# Logic.net
KiCad netlist of a schematic drawn in Altium Designer
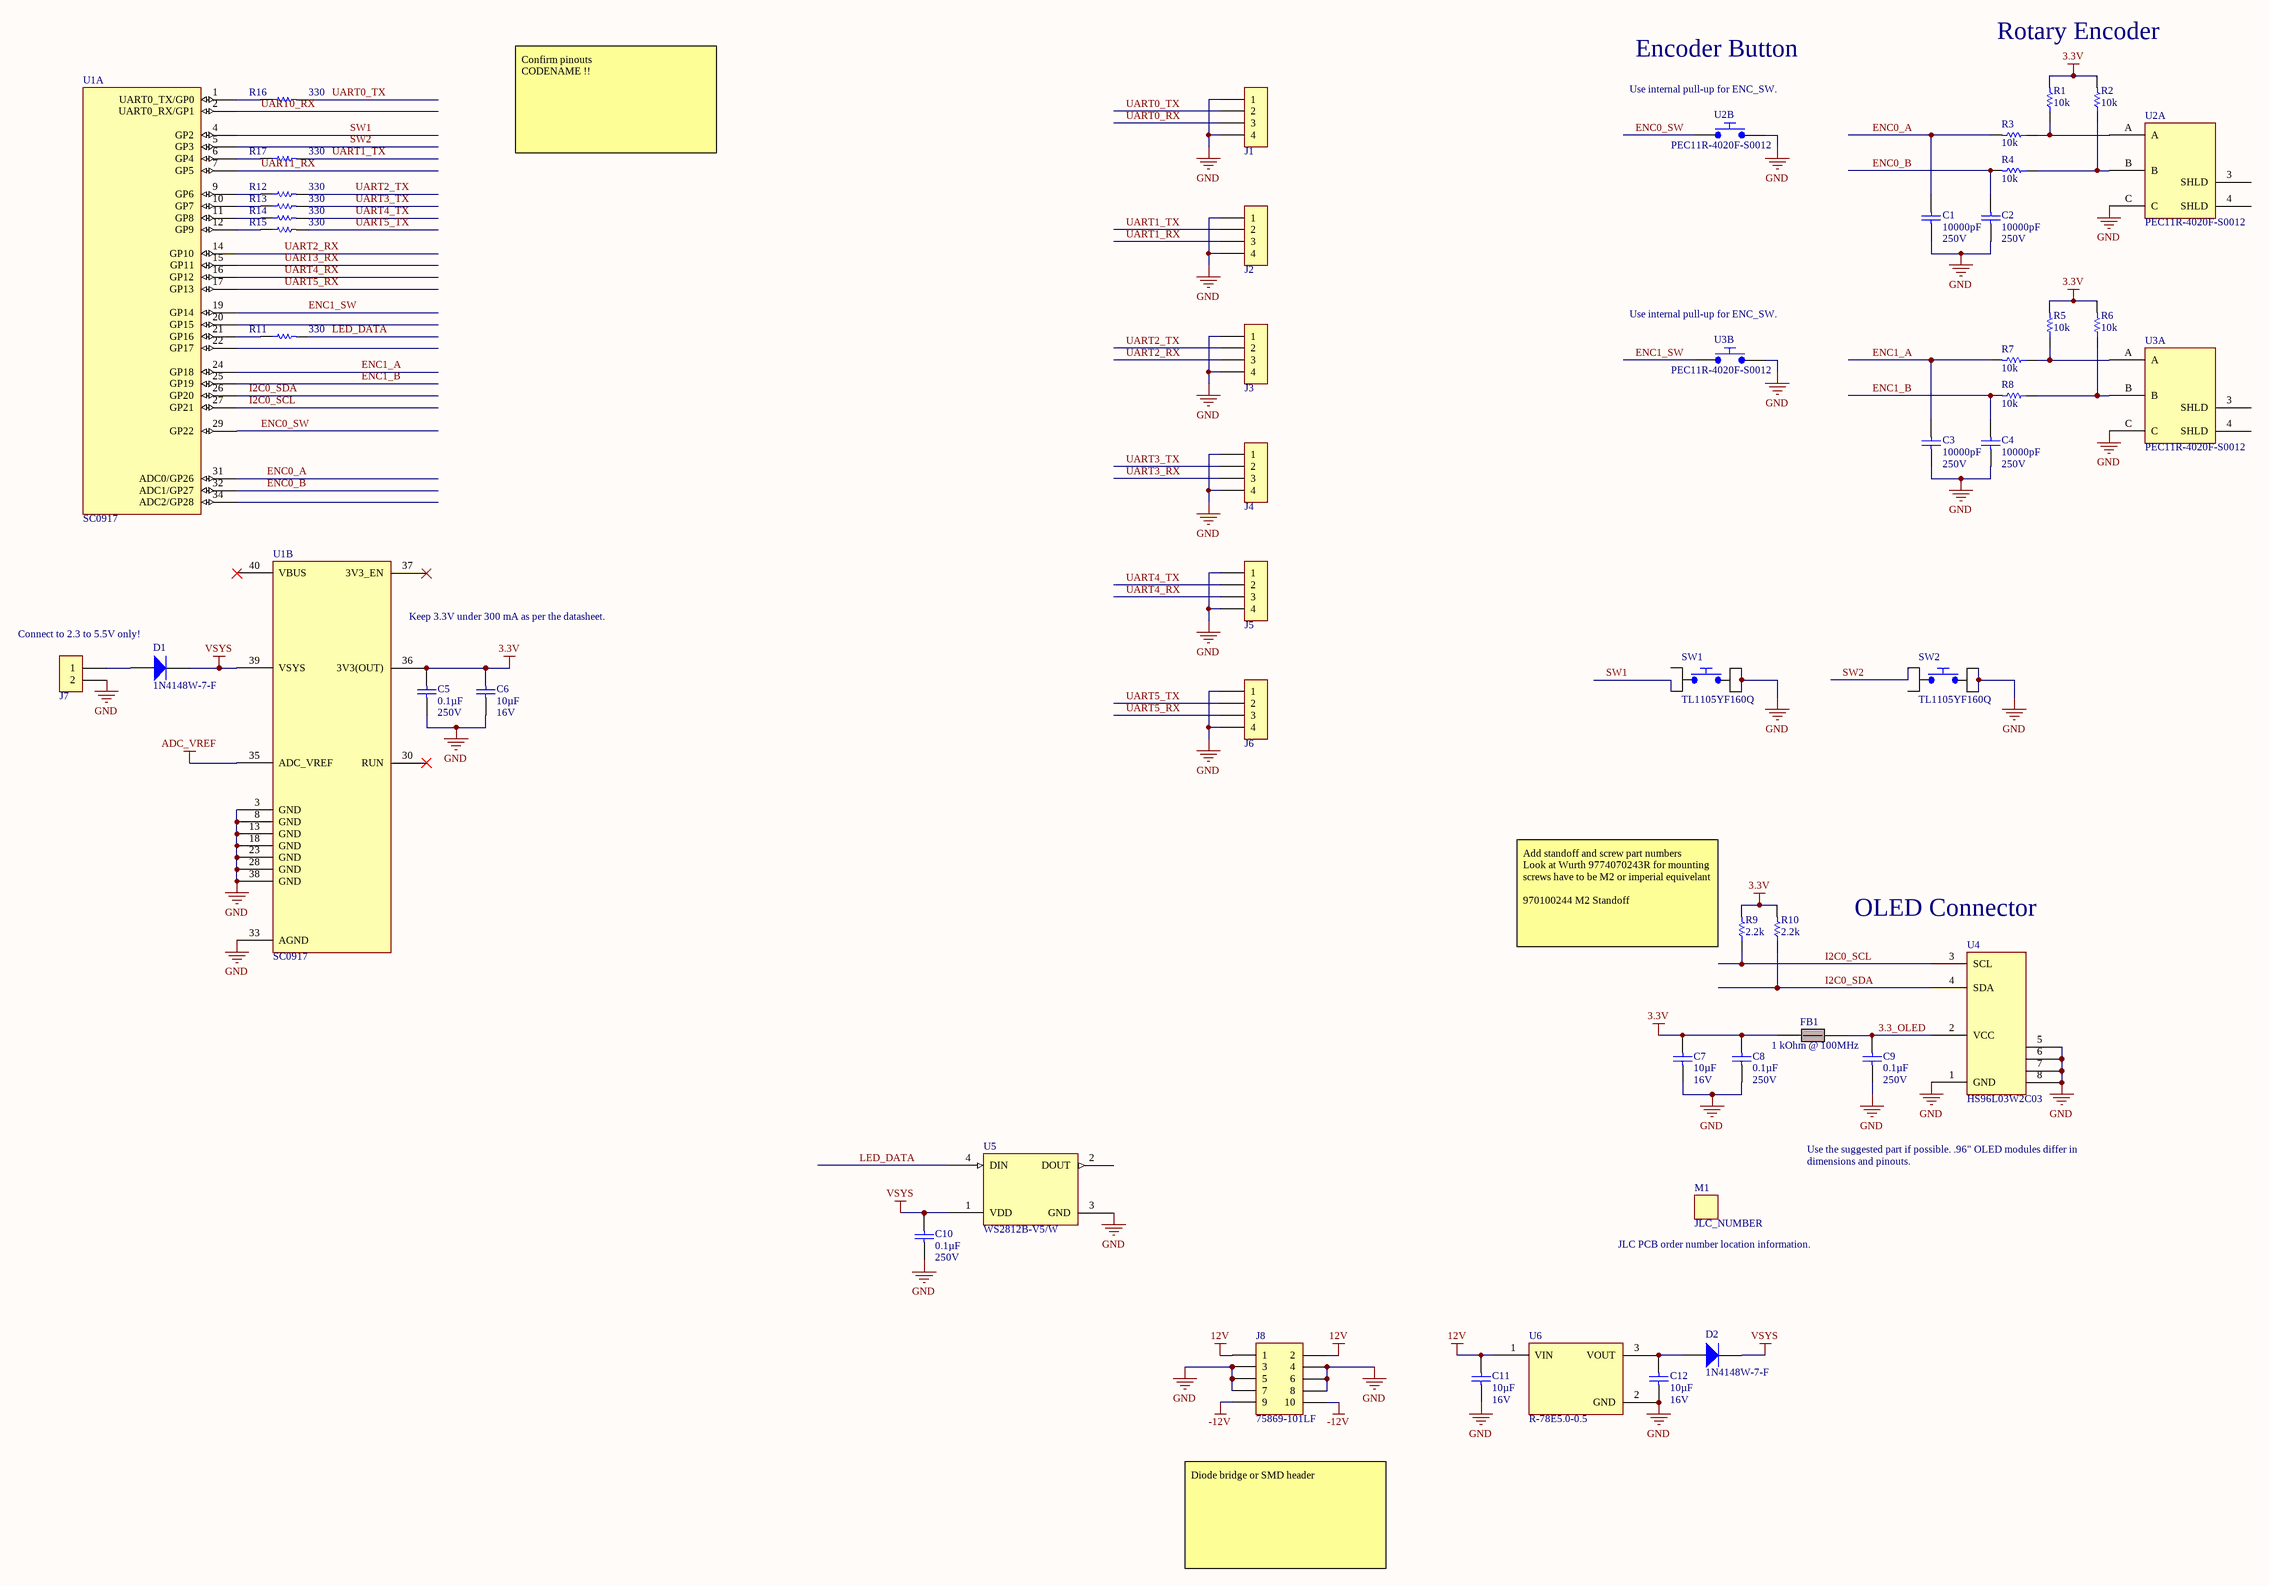
[diagram p0: Logic.SchDoc]

(export (version "E")
  (design (tool "Eeschema 10.0.6"))
  (components
    (comp (ref "C1")
      (value "10000pF")
      (footprint "Chip0805")
      (description "CAP CER 10000PF 250V X7R 0805")
      (fields
        (field (name "VOLTAGE") "250V")
        (field (name "PARTNUMBER") "C2012X7R2E103M125AE")
        (field (name "MANUFACTURER") "TDK Corporation")
      )
      (libsource (lib "Passives") (part "CAP"))
    )
    (comp (ref "C2")
      (value "10000pF")
      (footprint "Chip0805")
      (description "CAP CER 10000PF 250V X7R 0805")
      (fields
        (field (name "VOLTAGE") "250V")
        (field (name "PARTNUMBER") "C2012X7R2E103M125AE")
        (field (name "MANUFACTURER") "TDK Corporation")
      )
      (libsource (lib "Passives") (part "CAP"))
    )
    (comp (ref "C3")
      (value "10000pF")
      (footprint "Chip0805")
      (description "CAP CER 10000PF 250V X7R 0805")
      (fields
        (field (name "VOLTAGE") "250V")
        (field (name "PARTNUMBER") "C2012X7R2E103M125AE")
        (field (name "MANUFACTURER") "TDK Corporation")
      )
      (libsource (lib "Passives") (part "CAP"))
    )
    (comp (ref "C4")
      (value "10000pF")
      (footprint "Chip0805")
      (description "CAP CER 10000PF 250V X7R 0805")
      (fields
        (field (name "VOLTAGE") "250V")
        (field (name "PARTNUMBER") "C2012X7R2E103M125AE")
        (field (name "MANUFACTURER") "TDK Corporation")
      )
      (libsource (lib "Passives") (part "CAP"))
    )
    (comp (ref "C5")
      (value "0.1µF")
      (footprint "Chip0805")
      (description "CAP CER 0.1UF 250V 10% X7T 0805")
      (fields
        (field (name "VOLTAGE") "250V")
        (field (name "PARTNUMBER") "C2012X7T2E104K125AA")
        (field (name "MANUFACTURER") "TDK Corporation")
      )
      (libsource (lib "Passives") (part "CAP"))
    )
    (comp (ref "C6")
      (value "10µF")
      (footprint "Chip0805")
      (description "CAP CER 10UF 16V 10% X5R 0805")
      (fields
        (field (name "VOLTAGE") "16V")
        (field (name "PARTNUMBER") "C2012X5R1C106K125AC")
        (field (name "MANUFACTURER") "TDK Corporation")
      )
      (libsource (lib "Passives") (part "CAP"))
    )
    (comp (ref "C7")
      (value "10µF")
      (footprint "Chip0805")
      (description "CAP CER 10UF 16V 10% X5R 0805")
      (fields
        (field (name "VOLTAGE") "16V")
        (field (name "PARTNUMBER") "C2012X5R1C106K125AC")
        (field (name "MANUFACTURER") "TDK Corporation")
      )
      (libsource (lib "Passives") (part "CAP"))
    )
    (comp (ref "C8")
      (value "0.1µF")
      (footprint "Chip0805")
      (description "CAP CER 0.1UF 250V 10% X7T 0805")
      (fields
        (field (name "VOLTAGE") "250V")
        (field (name "PARTNUMBER") "C2012X7T2E104K125AA")
        (field (name "MANUFACTURER") "TDK Corporation")
      )
      (libsource (lib "Passives") (part "CAP"))
    )
    (comp (ref "C9")
      (value "0.1µF")
      (footprint "Chip0805")
      (description "CAP CER 0.1UF 250V 10% X7T 0805")
      (fields
        (field (name "VOLTAGE") "250V")
        (field (name "PARTNUMBER") "C2012X7T2E104K125AA")
        (field (name "MANUFACTURER") "TDK Corporation")
      )
      (libsource (lib "Passives") (part "CAP"))
    )
    (comp (ref "C10")
      (value "0.1µF")
      (footprint "Chip0805")
      (description "CAP CER 0.1UF 250V 10% X7T 0805")
      (fields
        (field (name "VOLTAGE") "250V")
        (field (name "PARTNUMBER") "C2012X7T2E104K125AA")
        (field (name "MANUFACTURER") "TDK Corporation")
      )
      (libsource (lib "Passives") (part "CAP"))
    )
    (comp (ref "C11")
      (value "10µF")
      (footprint "Chip0805")
      (description "CAP CER 10UF 16V 10% X5R 0805")
      (fields
        (field (name "VOLTAGE") "16V")
        (field (name "PARTNUMBER") "C2012X5R1C106K125AC")
        (field (name "MANUFACTURER") "TDK Corporation")
      )
      (libsource (lib "Passives") (part "CAP"))
    )
    (comp (ref "C12")
      (value "10µF")
      (footprint "Chip0805")
      (description "CAP CER 10UF 16V 10% X5R 0805")
      (fields
        (field (name "VOLTAGE") "16V")
        (field (name "PARTNUMBER") "C2012X5R1C106K125AC")
        (field (name "MANUFACTURER") "TDK Corporation")
      )
      (libsource (lib "Passives") (part "CAP"))
    )
    (comp (ref "D1")
      (value "1N4148W-7-F")
      (footprint "SOD-123")
      (description "DIODE SWITCH 100V 0.15A SOD123")
      (fields (field (name "MANUFACTURER") "Diodes Incorporated"))
      (libsource (lib "Semiconductor") (part "DIODE"))
    )
    (comp (ref "D2")
      (value "1N4148W-7-F")
      (footprint "SOD-123")
      (description "DIODE SWITCH 100V 0.15A SOD123")
      (fields (field (name "MANUFACTURER") "Diodes Incorporated"))
      (libsource (lib "Semiconductor") (part "DIODE"))
    )
    (comp (ref "FB1")
      (value "FERRITE")
      (footprint "Chip0805")
      (description "FERRITE BEAD 1000 OHM .20A 0805")
      (fields
        (field (name "IMPEDANCE @ FREQUENCY") "1 kOhm @ 100MHz")
        (field (name "PARTNUMBER") "74279205")
        (field (name "MANUFACTURER") "Wurth Electronics Inc")
      )
      (libsource (lib "Passives") (part "FERRITE"))
    )
    (comp (ref "J1")
      (value "0533980471")
      (footprint "Molex_0533980471")
      (description "CONN HEADER SMD 4POS 1.25MM")
      (fields (field (name "MANUFACTURER") "Molex"))
      (libsource (lib "Connectors") (part "HEADER_1x4"))
    )
    (comp (ref "J2")
      (value "0533980471")
      (footprint "Molex_0533980471")
      (description "CONN HEADER SMD 4POS 1.25MM")
      (fields (field (name "MANUFACTURER") "Molex"))
      (libsource (lib "Connectors") (part "HEADER_1x4"))
    )
    (comp (ref "J3")
      (value "0533980471")
      (footprint "Molex_0533980471")
      (description "CONN HEADER SMD 4POS 1.25MM")
      (fields (field (name "MANUFACTURER") "Molex"))
      (libsource (lib "Connectors") (part "HEADER_1x4"))
    )
    (comp (ref "J4")
      (value "0533980471")
      (footprint "Molex_0533980471")
      (description "CONN HEADER SMD 4POS 1.25MM")
      (fields (field (name "MANUFACTURER") "Molex"))
      (libsource (lib "Connectors") (part "HEADER_1x4"))
    )
    (comp (ref "J5")
      (value "0533980471")
      (footprint "Molex_0533980471")
      (description "CONN HEADER SMD 4POS 1.25MM")
      (fields (field (name "MANUFACTURER") "Molex"))
      (libsource (lib "Connectors") (part "HEADER_1x4"))
    )
    (comp (ref "J6")
      (value "0533980471")
      (footprint "Molex_0533980471")
      (description "CONN HEADER SMD 4POS 1.25MM")
      (fields (field (name "MANUFACTURER") "Molex"))
      (libsource (lib "Connectors") (part "HEADER_1x4"))
    )
    (comp (ref "J7")
      (value "3-644456-2")
      (footprint "TE_3-644456-2")
      (description "CONN HEADER VERT 2POS .100 TIN")
      (fields (field (name "MANUFACTURER") "TE Connectivity"))
      (libsource (lib "Connectors") (part "HEADER_1x2"))
    )
    (comp (ref "J8")
      (value "75869-101LF")
      (footprint "IDC_100_2x5")
      (description "CONN HEADER 10POS DUAL VERT PCB")
      (fields (field (name "MANUFACTURER") "FCI"))
      (libsource (lib "Connectors") (part "HEADER_2x5_ALT"))
    )
    (comp (ref "M1")
      (value "JLC_NUMBER")
      (footprint "JLC_NUMBER")
      (description "JLC Order Number Location")
      (libsource (lib "Mechanical") (part "MECH_NO_BOM"))
    )
    (comp (ref "R1")
      (value "10k")
      (footprint "Chip0805")
      (description "RES 10.0K OHM 1/8W 1% 0805 SMD")
      (fields (field (name "PARTNUMBER") "CRCW080510K0FKEA") (field (name "MANUFACTURER") "Vishay Dale"))
      (libsource (lib "Passives") (part "RES"))
    )
    (comp (ref "R2")
      (value "10k")
      (footprint "Chip0805")
      (description "RES 10.0K OHM 1/8W 1% 0805 SMD")
      (fields (field (name "PARTNUMBER") "CRCW080510K0FKEA") (field (name "MANUFACTURER") "Vishay Dale"))
      (libsource (lib "Passives") (part "RES"))
    )
    (comp (ref "R3")
      (value "10k")
      (footprint "Chip0805")
      (description "RES 10.0K OHM 1/8W 1% 0805 SMD")
      (fields (field (name "PARTNUMBER") "CRCW080510K0FKEA") (field (name "MANUFACTURER") "Vishay Dale"))
      (libsource (lib "Passives") (part "RES"))
    )
    (comp (ref "R4")
      (value "10k")
      (footprint "Chip0805")
      (description "RES 10.0K OHM 1/8W 1% 0805 SMD")
      (fields (field (name "PARTNUMBER") "CRCW080510K0FKEA") (field (name "MANUFACTURER") "Vishay Dale"))
      (libsource (lib "Passives") (part "RES"))
    )
    (comp (ref "R5")
      (value "10k")
      (footprint "Chip0805")
      (description "RES 10.0K OHM 1/8W 1% 0805 SMD")
      (fields (field (name "PARTNUMBER") "CRCW080510K0FKEA") (field (name "MANUFACTURER") "Vishay Dale"))
      (libsource (lib "Passives") (part "RES"))
    )
    (comp (ref "R6")
      (value "10k")
      (footprint "Chip0805")
      (description "RES 10.0K OHM 1/8W 1% 0805 SMD")
      (fields (field (name "PARTNUMBER") "CRCW080510K0FKEA") (field (name "MANUFACTURER") "Vishay Dale"))
      (libsource (lib "Passives") (part "RES"))
    )
    (comp (ref "R7")
      (value "10k")
      (footprint "Chip0805")
      (description "RES 10.0K OHM 1/8W 1% 0805 SMD")
      (fields (field (name "PARTNUMBER") "CRCW080510K0FKEA") (field (name "MANUFACTURER") "Vishay Dale"))
      (libsource (lib "Passives") (part "RES"))
    )
    (comp (ref "R8")
      (value "10k")
      (footprint "Chip0805")
      (description "RES 10.0K OHM 1/8W 1% 0805 SMD")
      (fields (field (name "PARTNUMBER") "CRCW080510K0FKEA") (field (name "MANUFACTURER") "Vishay Dale"))
      (libsource (lib "Passives") (part "RES"))
    )
    (comp (ref "R9")
      (value "2.2k")
      (footprint "Chip0805")
      (description "RES 2.20K OHM 1/8W 1% 0805 SMD")
      (fields (field (name "PARTNUMBER") "CRCW08052K20FKEA") (field (name "MANUFACTURER") "Vishay Dale"))
      (libsource (lib "Passives") (part "RES"))
    )
    (comp (ref "R10")
      (value "2.2k")
      (footprint "Chip0805")
      (description "RES 2.20K OHM 1/8W 1% 0805 SMD")
      (fields (field (name "PARTNUMBER") "CRCW08052K20FKEA") (field (name "MANUFACTURER") "Vishay Dale"))
      (libsource (lib "Passives") (part "RES"))
    )
    (comp (ref "R11")
      (value "330")
      (footprint "Chip0805")
      (description "RES 330 OHM 1/8W 1% 0805 SMD")
      (fields (field (name "PARTNUMBER") "CRCW0805330RFKEA") (field (name "MANUFACTURER") "Vishay Dale"))
      (libsource (lib "Passives") (part "RES"))
    )
    (comp (ref "R12")
      (value "330")
      (footprint "Chip0805")
      (description "RES 330 OHM 1/8W 1% 0805 SMD")
      (fields (field (name "PARTNUMBER") "CRCW0805330RFKEA") (field (name "MANUFACTURER") "Vishay Dale"))
      (libsource (lib "Passives") (part "RES"))
    )
    (comp (ref "R13")
      (value "330")
      (footprint "Chip0805")
      (description "RES 330 OHM 1/8W 1% 0805 SMD")
      (fields (field (name "PARTNUMBER") "CRCW0805330RFKEA") (field (name "MANUFACTURER") "Vishay Dale"))
      (libsource (lib "Passives") (part "RES"))
    )
    (comp (ref "R14")
      (value "330")
      (footprint "Chip0805")
      (description "RES 330 OHM 1/8W 1% 0805 SMD")
      (fields (field (name "PARTNUMBER") "CRCW0805330RFKEA") (field (name "MANUFACTURER") "Vishay Dale"))
      (libsource (lib "Passives") (part "RES"))
    )
    (comp (ref "R15")
      (value "330")
      (footprint "Chip0805")
      (description "RES 330 OHM 1/8W 1% 0805 SMD")
      (fields (field (name "PARTNUMBER") "CRCW0805330RFKEA") (field (name "MANUFACTURER") "Vishay Dale"))
      (libsource (lib "Passives") (part "RES"))
    )
    (comp (ref "R16")
      (value "330")
      (footprint "Chip0805")
      (description "RES 330 OHM 1/8W 1% 0805 SMD")
      (fields (field (name "PARTNUMBER") "CRCW0805330RFKEA") (field (name "MANUFACTURER") "Vishay Dale"))
      (libsource (lib "Passives") (part "RES"))
    )
    (comp (ref "R17")
      (value "330")
      (footprint "Chip0805")
      (description "RES 330 OHM 1/8W 1% 0805 SMD")
      (fields (field (name "PARTNUMBER") "CRCW0805330RFKEA") (field (name "MANUFACTURER") "Vishay Dale"))
      (libsource (lib "Passives") (part "RES"))
    )
    (comp (ref "SW1")
      (value "TL1105YF160Q")
      (footprint "E-Switch_TL1105YF")
      (description "SWITCH TACTILE SPST-NO 0.05A 12V")
      (fields (field (name "MANUFACTURER") "E-Switch"))
      (libsource (lib "Switches") (part "SWITCH_SPST_4PIN"))
    )
    (comp (ref "SW2")
      (value "TL1105YF160Q")
      (footprint "E-Switch_TL1105YF")
      (description "SWITCH TACTILE SPST-NO 0.05A 12V")
      (fields (field (name "MANUFACTURER") "E-Switch"))
      (libsource (lib "Switches") (part "SWITCH_SPST_4PIN"))
    )
    (comp (ref "U1")
      (value "SC0917")
      (footprint "RASPBERRY_PI_PICO_H")
      (description "RASPBERRY PI PICO H")
      (fields (field (name "MANUFACTURER") "Raspberry Pi"))
      (libsource (lib "ICs") (part "PI_PICO_H_SC0917"))
    )
    (comp (ref "U2")
      (value "PEC11R-4020F-S0012")
      (footprint "BOURNS_PEC11R-4020F-S")
      (description "ROTARY ENCODER MECHANICAL 12PPR")
      (fields (field (name "MANUFACTURER") "Bourns Inc."))
      (libsource (lib "Miscellaneous") (part "ROTARY_ENCODER_SWITCH"))
    )
    (comp (ref "U3")
      (value "PEC11R-4020F-S0012")
      (footprint "BOURNS_PEC11R-4020F-S")
      (description "ROTARY ENCODER MECHANICAL 12PPR")
      (fields (field (name "MANUFACTURER") "Bourns Inc."))
      (libsource (lib "") (part "ROTARY_ENCODER_SWITCH_1"))
    )
    (comp (ref "U4")
      (value "HS96L03W2C03")
      (footprint "HS_HS96L03W2C03")
      (description "0.96\" I2C OLED MODULE")
      (fields (field (name "MANUFACTURER") "HS"))
      (libsource (lib "ICs") (part "HS_HS96L03W2C03"))
    )
    (comp (ref "U5")
      (value "WS2812B-V5/W")
      (footprint "WS2812B")
      (description "Addressable RGB LED")
      (fields (field (name "MANUFACTURER") "Worldsemi"))
      (libsource (lib "Optoelectronics") (part "WORLDSEMI_WS2812B"))
    )
    (comp (ref "U6")
      (value "R-78E5.0-0.5")
      (footprint "3-SIP_Module")
      (description "DC DC CONVERTER 5V 3W")
      (fields (field (name "MANUFACTURER") "Recom Power"))
      (libsource (lib "ICs") (part "3-SIP_Module"))
    )
  )
  (nets
    (net (code "1") (name "-12V") (class "Default")
      (node (ref "J8") (pin "10") (pinfunction "10_10") (pintype "passive"))
      (node (ref "J8") (pin "9") (pinfunction "9_9") (pintype "passive"))
    )
    (net (code "2") (name "/3.3_OLED") (class "Default")
      (node (ref "C9") (pin "2") (pinfunction "2_2") (pintype "passive"))
      (node (ref "FB1") (pin "2") (pinfunction "2_2") (pintype "passive"))
      (node (ref "U4") (pin "2") (pinfunction "VCC_2") (pintype "passive"))
    )
    (net (code "3") (name "/ENC0_A") (class "Default")
      (node (ref "C1") (pin "2") (pinfunction "2_2") (pintype "passive"))
      (node (ref "R3") (pin "2") (pinfunction "2_2") (pintype "passive"))
      (node (ref "U1") (pin "31") (pinfunction "ADC0/GP26_31") (pintype "bidirectional"))
    )
    (net (code "4") (name "/ENC0_B") (class "Default")
      (node (ref "C2") (pin "2") (pinfunction "2_2") (pintype "passive"))
      (node (ref "R4") (pin "2") (pinfunction "2_2") (pintype "passive"))
      (node (ref "U1") (pin "32") (pinfunction "ADC1/GP27_32") (pintype "bidirectional"))
    )
    (net (code "5") (name "/ENC0_SW") (class "Default")
      (node (ref "U1") (pin "29") (pinfunction "GP22_29") (pintype "bidirectional"))
      (node (ref "U2") (pin "2") (pinfunction "2_2") (pintype "passive"))
    )
    (net (code "6") (name "/ENC1_A") (class "Default")
      (node (ref "C3") (pin "2") (pinfunction "2_2") (pintype "passive"))
      (node (ref "R7") (pin "2") (pinfunction "2_2") (pintype "passive"))
      (node (ref "U1") (pin "24") (pinfunction "GP18_24") (pintype "bidirectional"))
    )
    (net (code "7") (name "/ENC1_B") (class "Default")
      (node (ref "C4") (pin "2") (pinfunction "2_2") (pintype "passive"))
      (node (ref "R8") (pin "2") (pinfunction "2_2") (pintype "passive"))
      (node (ref "U1") (pin "25") (pinfunction "GP19_25") (pintype "bidirectional"))
    )
    (net (code "8") (name "/ENC1_SW") (class "Default")
      (node (ref "U1") (pin "19") (pinfunction "GP14_19") (pintype "bidirectional"))
      (node (ref "U3") (pin "2") (pinfunction "2_2") (pintype "passive"))
    )
    (net (code "9") (name "/I2C0_SCL") (class "Default")
      (node (ref "R9") (pin "1") (pinfunction "1_1") (pintype "passive"))
      (node (ref "U1") (pin "27") (pinfunction "GP21_27") (pintype "bidirectional"))
      (node (ref "U4") (pin "3") (pinfunction "SCL_3") (pintype "passive"))
    )
    (net (code "10") (name "/I2C0_SDA") (class "Default")
      (node (ref "R10") (pin "1") (pinfunction "1_1") (pintype "passive"))
      (node (ref "U1") (pin "26") (pinfunction "GP20_26") (pintype "bidirectional"))
      (node (ref "U4") (pin "4") (pinfunction "SDA_4") (pintype "passive"))
    )
    (net (code "11") (name "/LED_DATA") (class "Default")
      (node (ref "R11") (pin "2") (pinfunction "2_2") (pintype "passive"))
      (node (ref "U5") (pin "4") (pinfunction "DIN_4") (pintype "input"))
    )
    (net (code "12") (name "/SW1") (class "Default")
      (node (ref "SW1") (pin "2") (pinfunction "2_2") (pintype "passive"))
      (node (ref "U1") (pin "4") (pinfunction "GP2_4") (pintype "bidirectional"))
    )
    (net (code "13") (name "/SW2") (class "Default")
      (node (ref "SW2") (pin "1") (pinfunction "1_1") (pintype "passive"))
      (node (ref "U1") (pin "5") (pinfunction "GP3_5") (pintype "bidirectional"))
    )
    (net (code "14") (name "/UART0_RX") (class "Default")
      (node (ref "J1") (pin "3") (pinfunction "3_3") (pintype "passive"))
      (node (ref "U1") (pin "2") (pinfunction "UART0_RX/GP1_2") (pintype "bidirectional"))
    )
    (net (code "15") (name "/UART0_TX") (class "Default")
      (node (ref "J1") (pin "2") (pinfunction "2_2") (pintype "passive"))
      (node (ref "R16") (pin "2") (pinfunction "2_2") (pintype "passive"))
    )
    (net (code "16") (name "/UART1_RX") (class "Default")
      (node (ref "J2") (pin "3") (pinfunction "3_3") (pintype "passive"))
      (node (ref "U1") (pin "7") (pinfunction "GP5_7") (pintype "bidirectional"))
    )
    (net (code "17") (name "/UART1_TX") (class "Default")
      (node (ref "J2") (pin "2") (pinfunction "2_2") (pintype "passive"))
      (node (ref "R17") (pin "2") (pinfunction "2_2") (pintype "passive"))
    )
    (net (code "18") (name "/UART2_RX") (class "Default")
      (node (ref "J3") (pin "3") (pinfunction "3_3") (pintype "passive"))
      (node (ref "U1") (pin "14") (pinfunction "GP10_14") (pintype "bidirectional"))
    )
    (net (code "19") (name "/UART2_TX") (class "Default")
      (node (ref "J3") (pin "2") (pinfunction "2_2") (pintype "passive"))
      (node (ref "R12") (pin "2") (pinfunction "2_2") (pintype "passive"))
    )
    (net (code "20") (name "/UART3_RX") (class "Default")
      (node (ref "J4") (pin "3") (pinfunction "3_3") (pintype "passive"))
      (node (ref "U1") (pin "15") (pinfunction "GP11_15") (pintype "bidirectional"))
    )
    (net (code "21") (name "/UART3_TX") (class "Default")
      (node (ref "J4") (pin "2") (pinfunction "2_2") (pintype "passive"))
      (node (ref "R13") (pin "2") (pinfunction "2_2") (pintype "passive"))
    )
    (net (code "22") (name "/UART4_RX") (class "Default")
      (node (ref "J5") (pin "3") (pinfunction "3_3") (pintype "passive"))
      (node (ref "U1") (pin "16") (pinfunction "GP12_16") (pintype "bidirectional"))
    )
    (net (code "23") (name "/UART4_TX") (class "Default")
      (node (ref "J5") (pin "2") (pinfunction "2_2") (pintype "passive"))
      (node (ref "R14") (pin "2") (pinfunction "2_2") (pintype "passive"))
    )
    (net (code "24") (name "/UART5_RX") (class "Default")
      (node (ref "J6") (pin "3") (pinfunction "3_3") (pintype "passive"))
      (node (ref "U1") (pin "17") (pinfunction "GP13_17") (pintype "bidirectional"))
    )
    (net (code "25") (name "/UART5_TX") (class "Default")
      (node (ref "J6") (pin "2") (pinfunction "2_2") (pintype "passive"))
      (node (ref "R15") (pin "2") (pinfunction "2_2") (pintype "passive"))
    )
    (net (code "26") (name "3.3V") (class "Default")
      (node (ref "C5") (pin "2") (pinfunction "2_2") (pintype "passive"))
      (node (ref "C6") (pin "2") (pinfunction "2_2") (pintype "passive"))
      (node (ref "C7") (pin "2") (pinfunction "2_2") (pintype "passive"))
      (node (ref "C8") (pin "2") (pinfunction "2_2") (pintype "passive"))
      (node (ref "FB1") (pin "1") (pinfunction "1_1") (pintype "passive"))
      (node (ref "R1") (pin "2") (pinfunction "2_2") (pintype "passive"))
      (node (ref "R10") (pin "2") (pinfunction "2_2") (pintype "passive"))
      (node (ref "R2") (pin "2") (pinfunction "2_2") (pintype "passive"))
      (node (ref "R5") (pin "2") (pinfunction "2_2") (pintype "passive"))
      (node (ref "R6") (pin "2") (pinfunction "2_2") (pintype "passive"))
      (node (ref "R9") (pin "2") (pinfunction "2_2") (pintype "passive"))
      (node (ref "U1") (pin "36") (pinfunction "3V3(OUT)_36") (pintype "passive"))
    )
    (net (code "27") (name "12V") (class "Default")
      (node (ref "C11") (pin "2") (pinfunction "2_2") (pintype "passive"))
      (node (ref "J8") (pin "1") (pinfunction "1_1") (pintype "passive"))
      (node (ref "J8") (pin "2") (pinfunction "2_2") (pintype "passive"))
      (node (ref "U6") (pin "1") (pinfunction "VIN_1") (pintype "passive"))
    )
    (net (code "28") (name "ADC_VREF") (class "Default")
      (node (ref "U1") (pin "35") (pinfunction "ADC_VREF_35") (pintype "passive"))
    )
    (net (code "29") (name "GND") (class "Default")
      (node (ref "C1") (pin "1") (pinfunction "1_1") (pintype "passive"))
      (node (ref "C10") (pin "1") (pinfunction "1_1") (pintype "passive"))
      (node (ref "C11") (pin "1") (pinfunction "1_1") (pintype "passive"))
      (node (ref "C12") (pin "1") (pinfunction "1_1") (pintype "passive"))
      (node (ref "C2") (pin "1") (pinfunction "1_1") (pintype "passive"))
      (node (ref "C3") (pin "1") (pinfunction "1_1") (pintype "passive"))
      (node (ref "C4") (pin "1") (pinfunction "1_1") (pintype "passive"))
      (node (ref "C5") (pin "1") (pinfunction "1_1") (pintype "passive"))
      (node (ref "C6") (pin "1") (pinfunction "1_1") (pintype "passive"))
      (node (ref "C7") (pin "1") (pinfunction "1_1") (pintype "passive"))
      (node (ref "C8") (pin "1") (pinfunction "1_1") (pintype "passive"))
      (node (ref "C9") (pin "1") (pinfunction "1_1") (pintype "passive"))
      (node (ref "J1") (pin "1") (pinfunction "1_1") (pintype "passive"))
      (node (ref "J1") (pin "4") (pinfunction "4_4") (pintype "passive"))
      (node (ref "J2") (pin "1") (pinfunction "1_1") (pintype "passive"))
      (node (ref "J2") (pin "4") (pinfunction "4_4") (pintype "passive"))
      (node (ref "J3") (pin "1") (pinfunction "1_1") (pintype "passive"))
      (node (ref "J3") (pin "4") (pinfunction "4_4") (pintype "passive"))
      (node (ref "J4") (pin "1") (pinfunction "1_1") (pintype "passive"))
      (node (ref "J4") (pin "4") (pinfunction "4_4") (pintype "passive"))
      (node (ref "J5") (pin "1") (pinfunction "1_1") (pintype "passive"))
      (node (ref "J5") (pin "4") (pinfunction "4_4") (pintype "passive"))
      (node (ref "J6") (pin "1") (pinfunction "1_1") (pintype "passive"))
      (node (ref "J6") (pin "4") (pinfunction "4_4") (pintype "passive"))
      (node (ref "J7") (pin "2") (pinfunction "2_2") (pintype "passive"))
      (node (ref "J8") (pin "3") (pinfunction "3_3") (pintype "passive"))
      (node (ref "J8") (pin "4") (pinfunction "4_4") (pintype "passive"))
      (node (ref "J8") (pin "5") (pinfunction "5_5") (pintype "passive"))
      (node (ref "J8") (pin "6") (pinfunction "6_6") (pintype "passive"))
      (node (ref "J8") (pin "7") (pinfunction "7_7") (pintype "passive"))
      (node (ref "J8") (pin "8") (pinfunction "8_8") (pintype "passive"))
      (node (ref "SW1") (pin "3") (pinfunction "3_3") (pintype "passive"))
      (node (ref "SW1") (pin "4") (pinfunction "4_4") (pintype "passive"))
      (node (ref "SW2") (pin "3") (pinfunction "3_3") (pintype "passive"))
      (node (ref "SW2") (pin "4") (pinfunction "4_4") (pintype "passive"))
      (node (ref "U1") (pin "13") (pinfunction "GND_13") (pintype "passive"))
      (node (ref "U1") (pin "18") (pinfunction "GND_18") (pintype "passive"))
      (node (ref "U1") (pin "23") (pinfunction "GND_23") (pintype "passive"))
      (node (ref "U1") (pin "28") (pinfunction "GND_28") (pintype "passive"))
      (node (ref "U1") (pin "3") (pinfunction "GND_3") (pintype "passive"))
      (node (ref "U1") (pin "33") (pinfunction "AGND_33") (pintype "passive"))
      (node (ref "U1") (pin "38") (pinfunction "GND_38") (pintype "passive"))
      (node (ref "U1") (pin "8") (pinfunction "GND_8") (pintype "passive"))
      (node (ref "U2") (pin "1") (pinfunction "1_1") (pintype "passive"))
      (node (ref "U2") (pin "C") (pinfunction "C_C") (pintype "passive"))
      (node (ref "U3") (pin "1") (pinfunction "1_1") (pintype "passive"))
      (node (ref "U3") (pin "C") (pinfunction "C_C") (pintype "passive"))
      (node (ref "U4") (pin "1") (pinfunction "GND_1") (pintype "passive"))
      (node (ref "U4") (pin "5") (pinfunction "5_5") (pintype "passive"))
      (node (ref "U4") (pin "6") (pinfunction "6_6") (pintype "passive"))
      (node (ref "U4") (pin "7") (pinfunction "7_7") (pintype "passive"))
      (node (ref "U4") (pin "8") (pinfunction "8_8") (pintype "passive"))
      (node (ref "U5") (pin "3") (pinfunction "GND_3") (pintype "passive"))
      (node (ref "U6") (pin "2") (pinfunction "GND_2") (pintype "passive"))
    )
    (net (code "30") (name "Net-(D1-A)") (class "Default")
      (node (ref "D1") (pin "2") (pinfunction "A_2") (pintype "passive"))
      (node (ref "J7") (pin "1") (pinfunction "1_1") (pintype "passive"))
    )
    (net (code "31") (name "Net-(D2-A)") (class "Default")
      (node (ref "C12") (pin "2") (pinfunction "2_2") (pintype "passive"))
      (node (ref "D2") (pin "2") (pinfunction "A_2") (pintype "passive"))
      (node (ref "U6") (pin "3") (pinfunction "VOUT_3") (pintype "passive"))
    )
    (net (code "32") (name "Net-(R1-Pad1)") (class "Default")
      (node (ref "R1") (pin "1") (pinfunction "1_1") (pintype "passive"))
      (node (ref "R3") (pin "1") (pinfunction "1_1") (pintype "passive"))
      (node (ref "U2") (pin "A") (pinfunction "A_A") (pintype "passive"))
    )
    (net (code "33") (name "Net-(R2-Pad1)") (class "Default")
      (node (ref "R2") (pin "1") (pinfunction "1_1") (pintype "passive"))
      (node (ref "R4") (pin "1") (pinfunction "1_1") (pintype "passive"))
      (node (ref "U2") (pin "B") (pinfunction "B_B") (pintype "passive"))
    )
    (net (code "34") (name "Net-(R5-Pad1)") (class "Default")
      (node (ref "R5") (pin "1") (pinfunction "1_1") (pintype "passive"))
      (node (ref "R7") (pin "1") (pinfunction "1_1") (pintype "passive"))
      (node (ref "U3") (pin "A") (pinfunction "A_A") (pintype "passive"))
    )
    (net (code "35") (name "Net-(R6-Pad1)") (class "Default")
      (node (ref "R6") (pin "1") (pinfunction "1_1") (pintype "passive"))
      (node (ref "R8") (pin "1") (pinfunction "1_1") (pintype "passive"))
      (node (ref "U3") (pin "B") (pinfunction "B_B") (pintype "passive"))
    )
    (net (code "36") (name "Net-(U1A-GP4)") (class "Default")
      (node (ref "R17") (pin "1") (pinfunction "1_1") (pintype "passive"))
      (node (ref "U1") (pin "6") (pinfunction "GP4_6") (pintype "bidirectional"))
    )
    (net (code "37") (name "Net-(U1A-GP6)") (class "Default")
      (node (ref "R12") (pin "1") (pinfunction "1_1") (pintype "passive"))
      (node (ref "U1") (pin "9") (pinfunction "GP6_9") (pintype "bidirectional"))
    )
    (net (code "38") (name "Net-(U1A-GP7)") (class "Default")
      (node (ref "R13") (pin "1") (pinfunction "1_1") (pintype "passive"))
      (node (ref "U1") (pin "10") (pinfunction "GP7_10") (pintype "bidirectional"))
    )
    (net (code "39") (name "Net-(U1A-GP8)") (class "Default")
      (node (ref "R14") (pin "1") (pinfunction "1_1") (pintype "passive"))
      (node (ref "U1") (pin "11") (pinfunction "GP8_11") (pintype "bidirectional"))
    )
    (net (code "40") (name "Net-(U1A-GP9)") (class "Default")
      (node (ref "R15") (pin "1") (pinfunction "1_1") (pintype "passive"))
      (node (ref "U1") (pin "12") (pinfunction "GP9_12") (pintype "bidirectional"))
    )
    (net (code "41") (name "Net-(U1A-GP16)") (class "Default")
      (node (ref "R11") (pin "1") (pinfunction "1_1") (pintype "passive"))
      (node (ref "U1") (pin "21") (pinfunction "GP16_21") (pintype "bidirectional"))
    )
    (net (code "42") (name "Net-(U1A-UART0_TX{slash}GP0)") (class "Default")
      (node (ref "R16") (pin "1") (pinfunction "1_1") (pintype "passive"))
      (node (ref "U1") (pin "1") (pinfunction "UART0_TX/GP0_1") (pintype "bidirectional"))
    )
    (net (code "43") (name "VSYS") (class "Default")
      (node (ref "C10") (pin "2") (pinfunction "2_2") (pintype "passive"))
      (node (ref "D1") (pin "1") (pinfunction "C_1") (pintype "passive"))
      (node (ref "D2") (pin "1") (pinfunction "C_1") (pintype "passive"))
      (node (ref "U1") (pin "39") (pinfunction "VSYS_39") (pintype "passive"))
      (node (ref "U5") (pin "1") (pinfunction "VDD_1") (pintype "passive"))
    )
    (net (code "44") (name "unconnected-(SW1-Pad1)") (class "Default")
      (node (ref "SW1") (pin "1") (pinfunction "1_1") (pintype "passive"))
    )
    (net (code "45") (name "unconnected-(SW2-Pad2)") (class "Default")
      (node (ref "SW2") (pin "2") (pinfunction "2_2") (pintype "passive"))
    )
    (net (code "46") (name "unconnected-(U1A-ADC2{slash}GP28-Pad34)") (class "Default")
      (node (ref "U1") (pin "34") (pinfunction "ADC2/GP28_34") (pintype "bidirectional"))
    )
    (net (code "47") (name "unconnected-(U1A-GP15-Pad20)") (class "Default")
      (node (ref "U1") (pin "20") (pinfunction "GP15_20") (pintype "bidirectional"))
    )
    (net (code "48") (name "unconnected-(U1A-GP17-Pad22)") (class "Default")
      (node (ref "U1") (pin "22") (pinfunction "GP17_22") (pintype "bidirectional"))
    )
    (net (code "49") (name "unconnected-(U1B-3V3_EN-Pad37)") (class "Default")
      (node (ref "U1") (pin "37") (pinfunction "3V3_EN_37") (pintype "passive+no_connect"))
    )
    (net (code "50") (name "unconnected-(U1B-RUN-Pad30)") (class "Default")
      (node (ref "U1") (pin "30") (pinfunction "RUN_30") (pintype "passive+no_connect"))
    )
    (net (code "51") (name "unconnected-(U1B-VBUS-Pad40)") (class "Default")
      (node (ref "U1") (pin "40") (pinfunction "VBUS_40") (pintype "passive+no_connect"))
    )
    (net (code "52") (name "unconnected-(U2A-SHLD-Pad3)") (class "Default")
      (node (ref "U2") (pin "3") (pinfunction "SHLD_3") (pintype "passive"))
    )
    (net (code "53") (name "unconnected-(U2A-SHLD-Pad4)") (class "Default")
      (node (ref "U2") (pin "4") (pinfunction "SHLD_4") (pintype "passive"))
    )
    (net (code "54") (name "unconnected-(U3A-SHLD-Pad3)") (class "Default")
      (node (ref "U3") (pin "3") (pinfunction "SHLD_3") (pintype "passive"))
    )
    (net (code "55") (name "unconnected-(U3A-SHLD-Pad4)") (class "Default")
      (node (ref "U3") (pin "4") (pinfunction "SHLD_4") (pintype "passive"))
    )
    (net (code "56") (name "unconnected-(U5-DOUT-Pad2)") (class "Default")
      (node (ref "U5") (pin "2") (pinfunction "DOUT_2") (pintype "output"))
    )
  )
)
